# Baseplate.net
KiCad netlist of a schematic drawn in Altium Designer
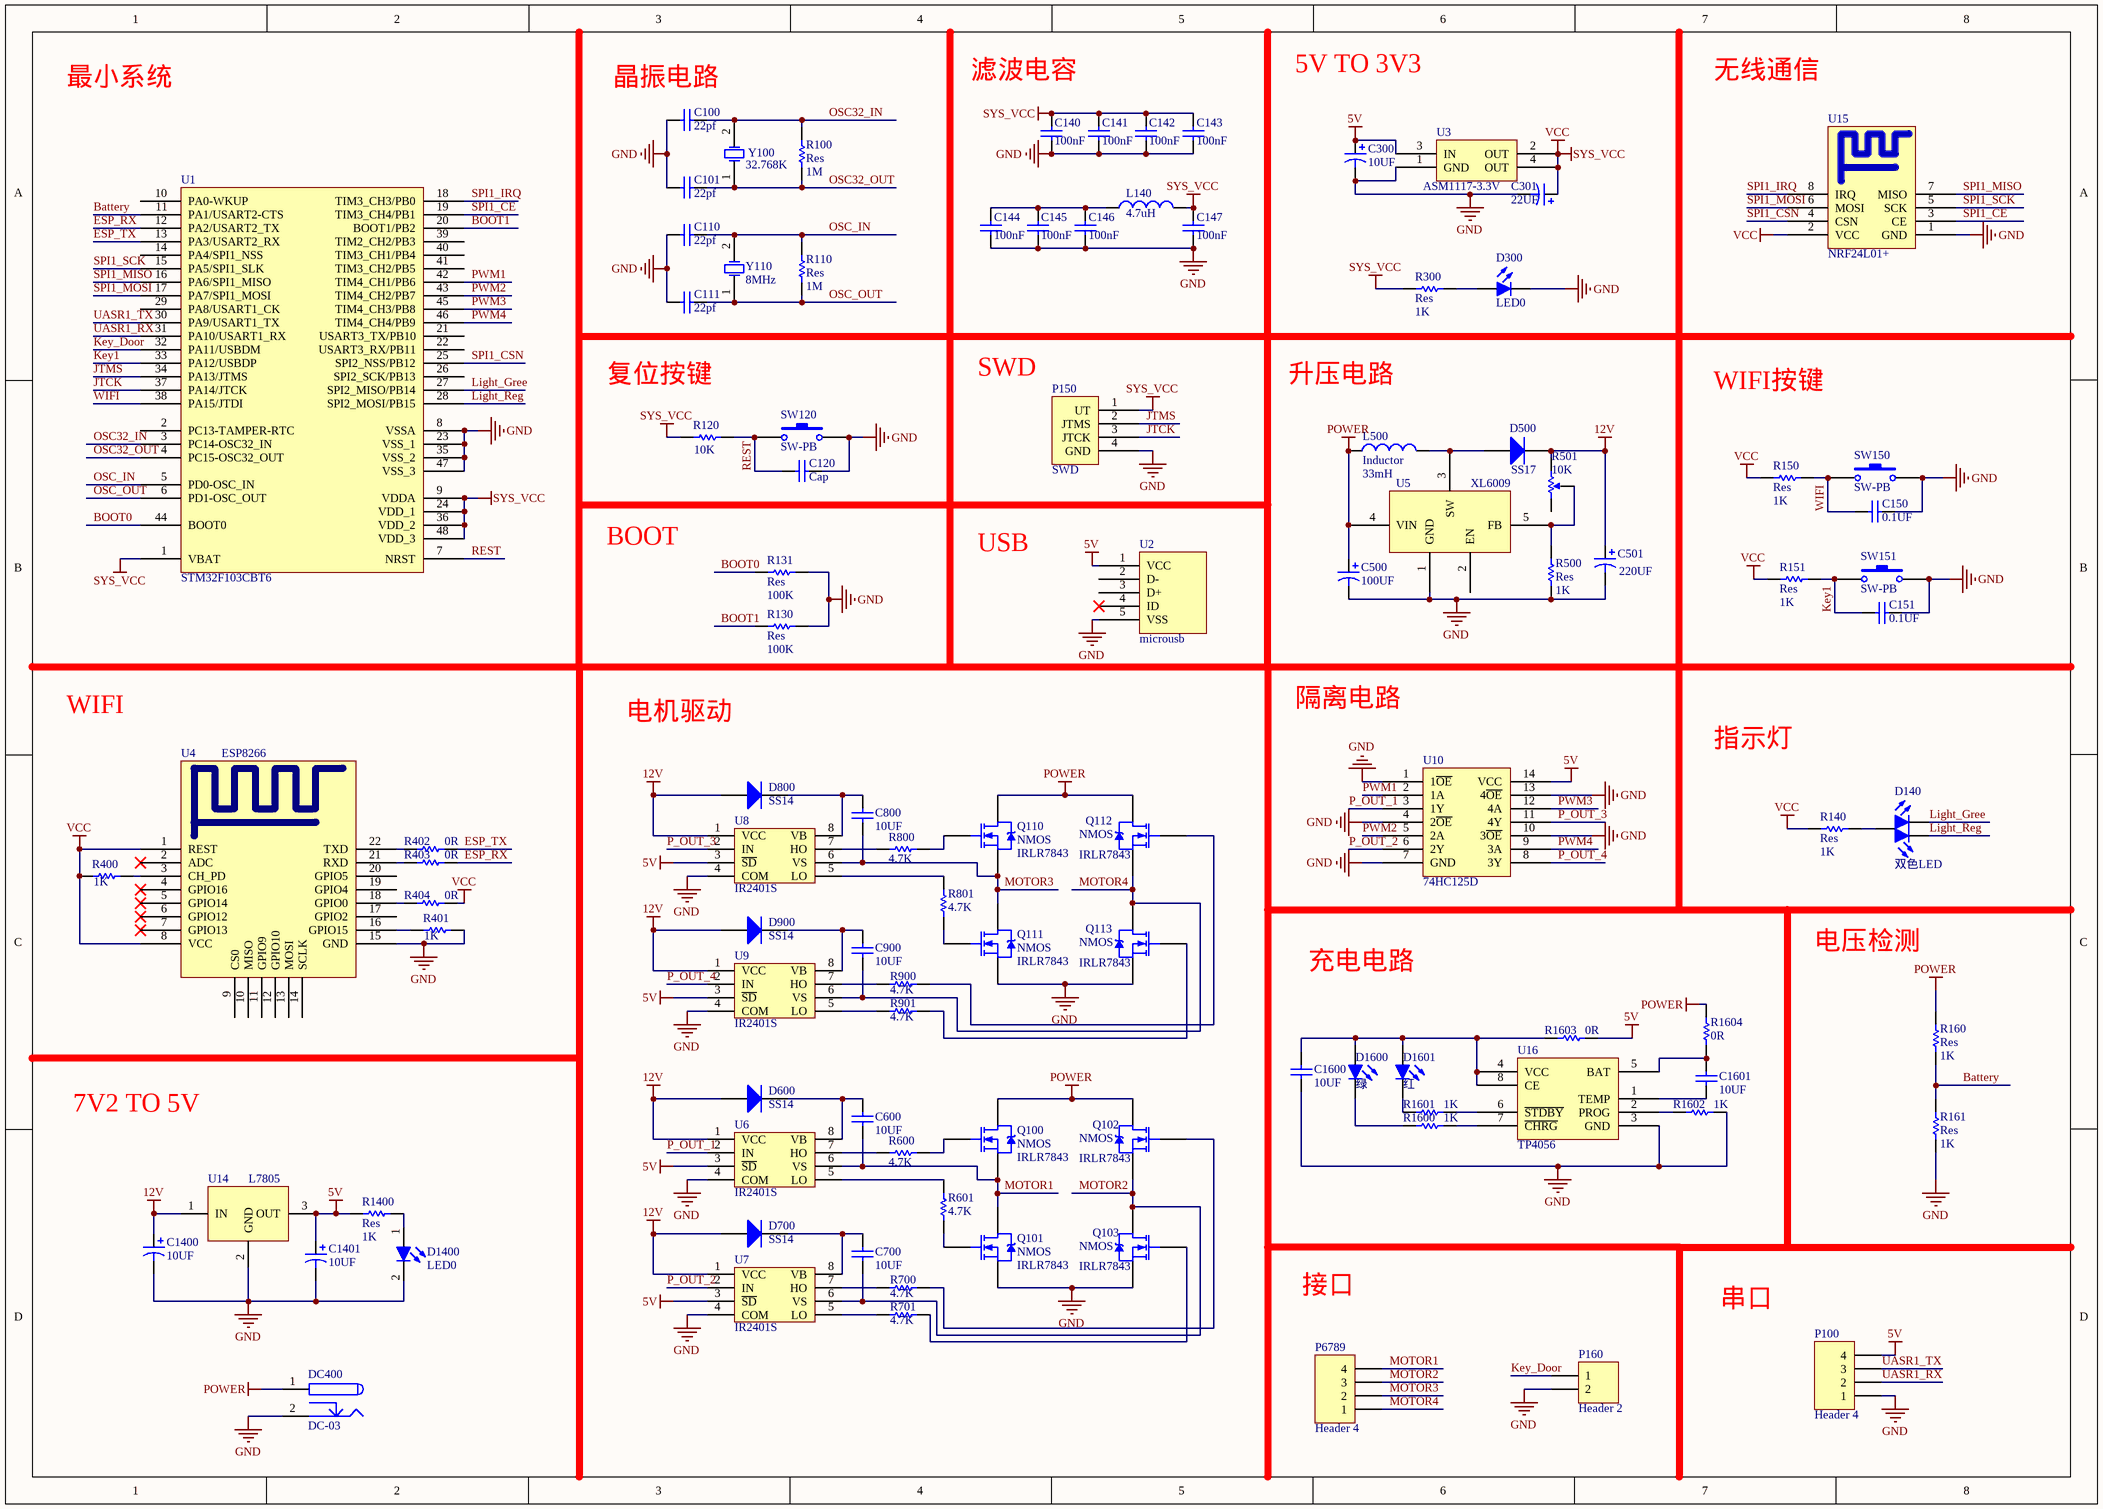
[diagram p0: Baseplate.SchDoc]

(export (version "E")
  (design (tool "Eeschema 10.0.6"))
  (components
    (comp (ref "C100")
      (value "22pf")
      (footprint "0805")
      (description "0805贴片电容")
      (libsource (lib "myintlib") (part "Cap"))
    )
    (comp (ref "C101")
      (value "22pf")
      (footprint "0805")
      (description "0805贴片电容")
      (libsource (lib "myintlib") (part "Cap"))
    )
    (comp (ref "C110")
      (value "22pf")
      (footprint "0805")
      (description "0805贴片电容")
      (libsource (lib "myintlib") (part "Cap"))
    )
    (comp (ref "C111")
      (value "22pf")
      (footprint "0805")
      (description "0805贴片电容")
      (libsource (lib "myintlib") (part "Cap"))
    )
    (comp (ref "C120")
      (value "Cap")
      (footprint "0805")
      (description "0805贴片电容")
      (libsource (lib "myintlib") (part "Cap"))
    )
    (comp (ref "C140")
      (value "100nF")
      (footprint "0805")
      (description "0805贴片电容")
      (libsource (lib "myintlib") (part "Cap"))
    )
    (comp (ref "C141")
      (value "100nF")
      (footprint "0805")
      (description "0805贴片电容")
      (libsource (lib "myintlib") (part "Cap"))
    )
    (comp (ref "C142")
      (value "100nF")
      (footprint "0805")
      (description "0805贴片电容")
      (libsource (lib "myintlib") (part "Cap"))
    )
    (comp (ref "C143")
      (value "100nF")
      (footprint "0805")
      (description "0805贴片电容")
      (libsource (lib "myintlib") (part "Cap"))
    )
    (comp (ref "C144")
      (value "100nF")
      (footprint "0805")
      (description "0805贴片电容")
      (libsource (lib "myintlib") (part "Cap"))
    )
    (comp (ref "C145")
      (value "100nF")
      (footprint "0805")
      (description "0805贴片电容")
      (libsource (lib "myintlib") (part "Cap"))
    )
    (comp (ref "C146")
      (value "100nF")
      (footprint "0805")
      (description "0805贴片电容")
      (libsource (lib "myintlib") (part "Cap"))
    )
    (comp (ref "C147")
      (value "100nF")
      (footprint "0805")
      (description "0805贴片电容")
      (libsource (lib "myintlib") (part "Cap"))
    )
    (comp (ref "C150")
      (value "0.1UF")
      (footprint "Cap0805")
      (description "0805贴片电容")
      (libsource (lib "myintlib") (part "Cap"))
    )
    (comp (ref "C151")
      (value "0.1UF")
      (footprint "Cap0805")
      (description "0805贴片电容")
      (libsource (lib "myintlib") (part "Cap"))
    )
    (comp (ref "C300")
      (value "10UF")
      (footprint "Cap0805")
      (description "10UF钽电容")
      (libsource (lib "myintlib") (part "Cap Pol3"))
    )
    (comp (ref "C301")
      (value "22UF")
      (footprint "Cap0805")
      (description "22UF钽电容")
      (libsource (lib "myintlib") (part "Cap Pol2"))
    )
    (comp (ref "C500")
      (value "100UF")
      (footprint "SMD6.3*7.7")
      (description "100UF电解电容")
      (libsource (lib "myintlib") (part "Cap Pol4"))
    )
    (comp (ref "C501")
      (value "Cap Pol5")
      (footprint "SMD8*10.5")
      (description "220UF电解电容")
      (fields (field (name "VAULE") "220UF"))
      (libsource (lib "myintlib") (part "Cap Pol5"))
    )
    (comp (ref "C600")
      (value "10UF")
      (footprint "0805")
      (description "0805贴片电容")
      (libsource (lib "myintlib") (part "Cap"))
    )
    (comp (ref "C700")
      (value "10UF")
      (footprint "0805")
      (description "0805贴片电容")
      (libsource (lib "myintlib") (part "Cap"))
    )
    (comp (ref "C800")
      (value "10UF")
      (footprint "0805")
      (description "0805贴片电容")
      (libsource (lib "myintlib") (part "Cap"))
    )
    (comp (ref "C900")
      (value "10UF")
      (footprint "0805")
      (description "0805贴片电容")
      (libsource (lib "myintlib") (part "Cap"))
    )
    (comp (ref "C1400")
      (value "10UF")
      (footprint "SMD4*4.5")
      (description "10UF钽电容")
      (libsource (lib "myintlib") (part "Cap Pol4"))
    )
    (comp (ref "C1401")
      (value "10UF")
      (footprint "SMD4*4.5")
      (description "10UF钽电容")
      (libsource (lib "myintlib") (part "Cap Pol4"))
    )
    (comp (ref "C1600")
      (value "10UF")
      (footprint "Cap0805")
      (description "0805贴片电容")
      (libsource (lib "myintlib") (part "Cap"))
    )
    (comp (ref "C1601")
      (value "10UF")
      (footprint "Cap0805")
      (description "0805贴片电容")
      (libsource (lib "myintlib") (part "Cap"))
    )
    (comp (ref "D140")
      (value "双色LED")
      (footprint "双色LED")
      (description "直插双色LED灯")
      (libsource (lib "myintlib") (part "双色LED"))
    )
    (comp (ref "D300")
      (value "LED0")
      (footprint "LED-0805")
      (description "0805贴片LED灯")
      (libsource (lib "myintlib") (part "LED0"))
    )
    (comp (ref "D500")
      (value "SS17")
      (footprint "DO-214AA")
      (description "1 Amp General Purpose Rectifier")
      (fields (field (name "PUBLISHER") "Altium Limited"))
      (libsource (lib "Miscellaneous Devices") (part "Diode 1N4007"))
    )
    (comp (ref "D600")
      (value "SS14")
      (footprint "DO-214AA")
      (description "肖特基二极管")
      (libsource (lib "myintlib") (part "Doide"))
    )
    (comp (ref "D700")
      (value "SS14")
      (footprint "DO-214AA")
      (description "肖特基二极管")
      (libsource (lib "myintlib") (part "Doide"))
    )
    (comp (ref "D800")
      (value "SS14")
      (footprint "DO-214AA")
      (description "肖特基二极管")
      (libsource (lib "myintlib") (part "Doide"))
    )
    (comp (ref "D900")
      (value "SS14")
      (footprint "DO-214AA")
      (description "肖特基二极管")
      (libsource (lib "myintlib") (part "Doide"))
    )
    (comp (ref "D1400")
      (value "LED0")
      (footprint "LED-0805")
      (description "0805贴片LED灯")
      (libsource (lib "") (part "LED0_1"))
    )
    (comp (ref "D1600")
      (value "绿")
      (footprint "LED-0805")
      (description "0805贴片LED灯")
      (libsource (lib "myintlib") (part "LED0"))
    )
    (comp (ref "D1601")
      (value "红")
      (footprint "LED-0805")
      (description "0805贴片LED灯")
      (libsource (lib "myintlib") (part "LED0"))
    )
    (comp (ref "DC400")
      (value "DC-03")
      (footprint "DC-003")
      (description "DC电源端子")
      (libsource (lib "myintlib") (part "DC-05"))
    )
    (comp (ref "L140")
      (value "4.7uH")
      (footprint "0805")
      (description "Inductor")
      (fields (field (name "PUBLISHER") "Altium Limited"))
      (libsource (lib "Miscellaneous Devices") (part "Inductor"))
    )
    (comp (ref "L500")
      (value "Inductor")
      (footprint "68uH-7*7")
      (fields (field (name "ALTIUM_VALUE") "33mH") (field (name "PUBLISHER") "Altium Limited"))
      (libsource (lib "Miscellaneous Devices") (part "Inductor"))
    )
    (comp (ref "P100")
      (value "Header 4")
      (footprint "HDR1X4")
      (description "Header, 4-Pin")
      (fields (field (name "PUBLISHER") "Altium Limited"))
      (libsource (lib "Miscellaneous Connectors") (part "Header 4"))
    )
    (comp (ref "P150")
      (value "SWD")
      (footprint "XH2.54-4P")
      (description "SWD下载端口")
      (libsource (lib "myintlib") (part "SWD"))
    )
    (comp (ref "P160")
      (value "Header 2")
      (footprint "HDR1X2")
      (description "Header, 2-Pin")
      (fields (field (name "PUBLISHER") "Altium Limited"))
      (libsource (lib "Miscellaneous Connectors") (part "Header 2"))
    )
    (comp (ref "P6789")
      (value "Header 4")
      (footprint "XH2.54-4P")
      (description "Header, 4-Pin")
      (fields (field (name "PUBLISHER") "Altium Limited"))
      (libsource (lib "Miscellaneous Connectors") (part "Header 4"))
    )
    (comp (ref "Q100")
      (value "NMOS")
      (footprint "DPAK/TO-252AA")
      (description "N沟MOS管")
      (fields (field (name "VAULE") "IRLR7843"))
      (libsource (lib "myintlib") (part "NMOS"))
    )
    (comp (ref "Q101")
      (value "NMOS")
      (footprint "DPAK/TO-252AA")
      (description "N沟MOS管")
      (fields (field (name "VAULE") "IRLR7843"))
      (libsource (lib "myintlib") (part "NMOS"))
    )
    (comp (ref "Q102")
      (value "NMOS")
      (footprint "DPAK/TO-252AA")
      (description "N沟MOS管")
      (fields (field (name "VAULE") "IRLR7843"))
      (libsource (lib "myintlib") (part "NMOS"))
    )
    (comp (ref "Q103")
      (value "NMOS")
      (footprint "DPAK/TO-252AA")
      (description "N沟MOS管")
      (fields (field (name "VAULE") "IRLR7843"))
      (libsource (lib "myintlib") (part "NMOS"))
    )
    (comp (ref "Q110")
      (value "NMOS")
      (footprint "DPAK/TO-252AA")
      (description "N沟MOS管")
      (fields (field (name "VAULE") "IRLR7843"))
      (libsource (lib "myintlib") (part "NMOS"))
    )
    (comp (ref "Q111")
      (value "NMOS")
      (footprint "DPAK/TO-252AA")
      (description "N沟MOS管")
      (fields (field (name "VAULE") "IRLR7843"))
      (libsource (lib "myintlib") (part "NMOS"))
    )
    (comp (ref "Q112")
      (value "NMOS")
      (footprint "DPAK/TO-252AA")
      (description "N沟MOS管")
      (fields (field (name "VAULE") "IRLR7843"))
      (libsource (lib "myintlib") (part "NMOS"))
    )
    (comp (ref "Q113")
      (value "NMOS")
      (footprint "DPAK/TO-252AA")
      (description "N沟MOS管")
      (fields (field (name "VAULE") "IRLR7843"))
      (libsource (lib "myintlib") (part "NMOS"))
    )
    (comp (ref "R100")
      (value "Res")
      (footprint "0805")
      (fields (field (name "ALTIUM_UNNAMED_1") "1M"))
      (libsource (lib "myintlib") (part "Res"))
    )
    (comp (ref "R110")
      (value "Res")
      (footprint "0805")
      (fields (field (name "ALTIUM_UNNAMED_1") "1M"))
      (libsource (lib "myintlib") (part "Res"))
    )
    (comp (ref "R120")
      (value "Res")
      (footprint "0805")
      (fields (field (name "ALTIUM_UNNAMED_1") "10K"))
      (libsource (lib "myintlib") (part "Res"))
    )
    (comp (ref "R130")
      (value "Res")
      (footprint "0805")
      (fields (field (name "ALTIUM_UNNAMED_1") "100K"))
      (libsource (lib "myintlib") (part "Res"))
    )
    (comp (ref "R131")
      (value "Res")
      (footprint "0805")
      (fields (field (name "ALTIUM_UNNAMED_1") "100K"))
      (libsource (lib "myintlib") (part "Res"))
    )
    (comp (ref "R140")
      (value "Res")
      (footprint "0805")
      (description "0805贴片电阻")
      (fields (field (name "VAULE") "1K"))
      (libsource (lib "myintlib") (part "Res"))
    )
    (comp (ref "R150")
      (value "Res")
      (footprint "0805")
      (description "0805贴片电阻")
      (fields (field (name "VAULE") "1K"))
      (libsource (lib "myintlib") (part "Res"))
    )
    (comp (ref "R151")
      (value "Res")
      (footprint "0805")
      (description "0805贴片电阻")
      (fields (field (name "VAULE") "1K"))
      (libsource (lib "myintlib") (part "Res"))
    )
    (comp (ref "R160")
      (value "Res")
      (footprint "0805")
      (description "0805贴片电阻")
      (fields (field (name "VAULE") "1K"))
      (libsource (lib "myintlib") (part "Res"))
    )
    (comp (ref "R161")
      (value "Res")
      (footprint "0805")
      (description "0805贴片电阻")
      (fields (field (name "VAULE") "1K"))
      (libsource (lib "myintlib") (part "Res"))
    )
    (comp (ref "R300")
      (value "Res")
      (footprint "0805")
      (fields (field (name "ALTIUM_UNNAMED_1") "1K"))
      (libsource (lib "myintlib") (part "Res"))
    )
    (comp (ref "R400")
      (value "Res")
      (footprint "0805")
      (description "0805贴片电阻")
      (fields (field (name "VAULE") "1K"))
      (libsource (lib "myintlib") (part "Res"))
    )
    (comp (ref "R401")
      (value "Res")
      (footprint "0805")
      (description "0805贴片电阻")
      (fields (field (name "VAULE") "1K"))
      (libsource (lib "myintlib") (part "Res"))
    )
    (comp (ref "R402")
      (value "Res")
      (footprint "0805")
      (description "0805贴片电阻")
      (fields (field (name "VAULE") "0R"))
      (libsource (lib "myintlib") (part "Res"))
    )
    (comp (ref "R403")
      (value "Res")
      (footprint "0805")
      (description "0805贴片电阻")
      (fields (field (name "VAULE") "0R"))
      (libsource (lib "myintlib") (part "Res"))
    )
    (comp (ref "R404")
      (value "Res")
      (footprint "0805")
      (description "0805贴片电阻")
      (fields (field (name "VAULE") "0R"))
      (libsource (lib "myintlib") (part "Res"))
    )
    (comp (ref "R500")
      (value "Res")
      (footprint "0805")
      (fields (field (name "ALTIUM_UNNAMED_1") "1K"))
      (libsource (lib "myintlib") (part "Res"))
    )
    (comp (ref "R501")
      (value "10K")
      (footprint "3296W")
      (description "3362电阻")
      (libsource (lib "myintlib") (part "ResAdj"))
    )
    (comp (ref "R600")
      (value "~")
      (footprint "0805")
      (fields (field (name "ALTIUM_UNNAMED_1") "4.7K"))
      (libsource (lib "myintlib") (part "Res"))
    )
    (comp (ref "R601")
      (value "~")
      (footprint "0805")
      (fields (field (name "ALTIUM_UNNAMED_1") "4.7K"))
      (libsource (lib "myintlib") (part "Res"))
    )
    (comp (ref "R700")
      (value "~")
      (footprint "0805")
      (fields (field (name "ALTIUM_UNNAMED_1") "4.7K"))
      (libsource (lib "myintlib") (part "Res"))
    )
    (comp (ref "R701")
      (value "~")
      (footprint "0805")
      (fields (field (name "ALTIUM_UNNAMED_1") "4.7K"))
      (libsource (lib "myintlib") (part "Res"))
    )
    (comp (ref "R800")
      (value "~")
      (footprint "0805")
      (fields (field (name "ALTIUM_UNNAMED_1") "4.7K"))
      (libsource (lib "myintlib") (part "Res"))
    )
    (comp (ref "R801")
      (value "~")
      (footprint "0805")
      (fields (field (name "ALTIUM_UNNAMED_1") "4.7K"))
      (libsource (lib "myintlib") (part "Res"))
    )
    (comp (ref "R900")
      (value "~")
      (footprint "0805")
      (fields (field (name "ALTIUM_UNNAMED_1") "4.7K"))
      (libsource (lib "myintlib") (part "Res"))
    )
    (comp (ref "R901")
      (value "~")
      (footprint "0805")
      (fields (field (name "ALTIUM_UNNAMED_1") "4.7K"))
      (libsource (lib "myintlib") (part "Res"))
    )
    (comp (ref "R1400")
      (value "Res")
      (footprint "0805")
      (fields (field (name "ALTIUM_UNNAMED_1") "1K"))
      (libsource (lib "myintlib") (part "Res"))
    )
    (comp (ref "R1600")
      (value "Res")
      (footprint "0805")
      (description "0805贴片电阻")
      (fields (field (name "VAULE") "1K"))
      (libsource (lib "myintlib") (part "Res"))
    )
    (comp (ref "R1601")
      (value "Res")
      (footprint "0805")
      (description "0805贴片电阻")
      (fields (field (name "VAULE") "1K"))
      (libsource (lib "myintlib") (part "Res"))
    )
    (comp (ref "R1602")
      (value "Res")
      (footprint "0805")
      (description "0805贴片电阻")
      (fields (field (name "VAULE") "1K"))
      (libsource (lib "myintlib") (part "Res"))
    )
    (comp (ref "R1603")
      (value "Res")
      (footprint "0805")
      (description "0805贴片电阻")
      (fields (field (name "VAULE") "0R"))
      (libsource (lib "myintlib") (part "Res"))
    )
    (comp (ref "R1604")
      (value "Res")
      (footprint "0805")
      (description "0805贴片电阻")
      (fields (field (name "VAULE") "0R"))
      (libsource (lib "myintlib") (part "Res"))
    )
    (comp (ref "SW120")
      (value "SW-PB")
      (footprint "SW-PB")
      (description "贴片按键")
      (libsource (lib "myintlib") (part "SW-PB"))
    )
    (comp (ref "SW150")
      (value "SW-PB")
      (footprint "SW-PB")
      (description "贴片按键")
      (libsource (lib "myintlib") (part "SW-PB"))
    )
    (comp (ref "SW151")
      (value "SW-PB")
      (footprint "SW-PB")
      (description "贴片按键")
      (libsource (lib "myintlib") (part "SW-PB"))
    )
    (comp (ref "U1")
      (value "STM32F103CBT6")
      (footprint "LQFP-48")
      (description "Cortex-M3内核单片机")
      (libsource (lib "myintlib") (part "STM32F103C8T6"))
    )
    (comp (ref "U2") (value "microusb") (footprint "microusb") (libsource (lib "myintlib") (part "microusb")))
    (comp (ref "U3")
      (value "ASM1117-3.3V")
      (footprint "SOT-223")
      (description "线性稳压芯片")
      (libsource (lib "myintlib") (part "ASM1117"))
    )
    (comp (ref "U4")
      (value "ESP8266")
      (footprint "myintlib:ESP8266")
      (description "串口wifi模块")
      (libsource (lib "myintlib") (part "ESP8266"))
    )
    (comp (ref "U5")
      (value "XL6009")
      (footprint "TO-263-5")
      (description "升压芯片")
      (libsource (lib "myintlib") (part "XL6009"))
    )
    (comp (ref "U6")
      (value "IR2401S")
      (footprint "myintlib:SOP8")
      (description "半桥驱动器")
      (libsource (lib "myintlib") (part "IR2401S"))
    )
    (comp (ref "U7")
      (value "IR2401S")
      (footprint "myintlib:SOP8")
      (description "半桥驱动器")
      (libsource (lib "myintlib") (part "IR2401S"))
    )
    (comp (ref "U8")
      (value "IR2401S")
      (footprint "myintlib:SOP8")
      (description "半桥驱动器")
      (libsource (lib "myintlib") (part "IR2401S"))
    )
    (comp (ref "U9")
      (value "IR2401S")
      (footprint "myintlib:SOP8")
      (description "半桥驱动器")
      (libsource (lib "myintlib") (part "IR2401S"))
    )
    (comp (ref "U10") (value "74HC125D") (footprint "SOP14") (libsource (lib "myintlib") (part "74HC125D")))
    (comp (ref "U14")
      (value "L7805")
      (footprint "TO-220-3")
      (description "5V线性稳压芯片")
      (libsource (lib "myintlib") (part "L7805"))
    )
    (comp (ref "U15")
      (value "NRF24L01+")
      (footprint "DIP8NRF")
      (description "直插式NRF")
      (libsource (lib "myintlib") (part "NRF24L01+"))
    )
    (comp (ref "U16")
      (value "TP4056")
      (footprint "SOP8")
      (description "锂电池充电芯片")
      (libsource (lib "myintlib") (part "TP4056"))
    )
    (comp (ref "Y100") (value "32.768K") (footprint "308晶振") (libsource (lib "myintlib") (part "32.768K")))
    (comp (ref "Y110")
      (value "8MHz")
      (footprint "X-HC49U")
      (description "无源晶振")
      (libsource (lib "myintlib") (part "XTAL"))
    )
  )
  (nets
    (net (code "1") (name "/BOOT0") (class "Default")
      (node (ref "R131") (pin "1") (pinfunction "1_1") (pintype "passive"))
      (node (ref "U1") (pin "44") (pinfunction "BOOT0_44") (pintype "passive"))
    )
    (net (code "2") (name "/BOOT1") (class "Default")
      (node (ref "R130") (pin "2") (pinfunction "2_2") (pintype "passive"))
      (node (ref "U1") (pin "20") (pinfunction "BOOT1/PB2_20") (pintype "passive"))
    )
    (net (code "3") (name "/Battery") (class "Default")
      (node (ref "R160") (pin "1") (pinfunction "1_1") (pintype "passive"))
      (node (ref "R161") (pin "2") (pinfunction "2_2") (pintype "passive"))
      (node (ref "U1") (pin "11") (pinfunction "PA1/USART2-CTS_11") (pintype "passive"))
    )
    (net (code "4") (name "/ESP_RX") (class "Default")
      (node (ref "R403") (pin "2") (pinfunction "2_2") (pintype "passive"))
      (node (ref "U1") (pin "12") (pinfunction "PA2/USART2_TX_12") (pintype "passive"))
    )
    (net (code "5") (name "/ESP_TX") (class "Default")
      (node (ref "R402") (pin "2") (pinfunction "2_2") (pintype "passive"))
      (node (ref "U1") (pin "13") (pinfunction "PA3/USART2_RX_13") (pintype "passive"))
    )
    (net (code "6") (name "/JTCK") (class "Default")
      (node (ref "P150") (pin "3") (pinfunction "JTCK_3") (pintype "power_in"))
      (node (ref "U1") (pin "37") (pinfunction "PA14/JTCK_37") (pintype "passive"))
    )
    (net (code "7") (name "/JTMS") (class "Default")
      (node (ref "P150") (pin "2") (pinfunction "JTMS_2") (pintype "power_in"))
      (node (ref "U1") (pin "34") (pinfunction "PA13/JTMS_34") (pintype "passive"))
    )
    (net (code "8") (name "/Key1") (class "Default")
      (node (ref "C151") (pin "1") (pinfunction "1_1") (pintype "passive"))
      (node (ref "R151") (pin "2") (pinfunction "2_2") (pintype "passive"))
      (node (ref "SW151") (pin "1") (pinfunction "1_1") (pintype "passive"))
      (node (ref "U1") (pin "33") (pinfunction "PA12/USBDP_33") (pintype "passive"))
    )
    (net (code "9") (name "/Key_Door") (class "Default")
      (node (ref "P160") (pin "1") (pinfunction "1_1") (pintype "passive"))
      (node (ref "U1") (pin "32") (pinfunction "PA11/USBDM_32") (pintype "passive"))
    )
    (net (code "10") (name "/Light_Gree") (class "Default")
      (node (ref "D140") (pin "1") (pinfunction "A_1") (pintype "passive"))
      (node (ref "U1") (pin "27") (pinfunction "SPI2_MISO/PB14_27") (pintype "passive"))
    )
    (net (code "11") (name "/Light_Reg") (class "Default")
      (node (ref "D140") (pin "3") (pinfunction "A_3") (pintype "passive"))
      (node (ref "U1") (pin "28") (pinfunction "SPI2_MOSI/PB15_28") (pintype "passive"))
    )
    (net (code "12") (name "/MOTOR1") (class "Default")
      (node (ref "C600") (pin "2") (pinfunction "2_2") (pintype "passive"))
      (node (ref "P6789") (pin "4") (pinfunction "4_4") (pintype "passive"))
      (node (ref "Q100") (pin "3") (pinfunction "S_3") (pintype "passive"))
      (node (ref "Q101") (pin "2") (pinfunction "D_2") (pintype "passive"))
      (node (ref "U6") (pin "6") (pinfunction "VS_6") (pintype "passive"))
    )
    (net (code "13") (name "/MOTOR2") (class "Default")
      (node (ref "C700") (pin "2") (pinfunction "2_2") (pintype "passive"))
      (node (ref "P6789") (pin "3") (pinfunction "3_3") (pintype "passive"))
      (node (ref "Q102") (pin "3") (pinfunction "S_3") (pintype "passive"))
      (node (ref "Q103") (pin "2") (pinfunction "D_2") (pintype "passive"))
      (node (ref "U7") (pin "6") (pinfunction "VS_6") (pintype "passive"))
    )
    (net (code "14") (name "/MOTOR3") (class "Default")
      (node (ref "C800") (pin "2") (pinfunction "2_2") (pintype "passive"))
      (node (ref "P6789") (pin "2") (pinfunction "2_2") (pintype "passive"))
      (node (ref "Q110") (pin "3") (pinfunction "S_3") (pintype "passive"))
      (node (ref "Q111") (pin "2") (pinfunction "D_2") (pintype "passive"))
      (node (ref "U8") (pin "6") (pinfunction "VS_6") (pintype "passive"))
    )
    (net (code "15") (name "/MOTOR4") (class "Default")
      (node (ref "C900") (pin "2") (pinfunction "2_2") (pintype "passive"))
      (node (ref "P6789") (pin "1") (pinfunction "1_1") (pintype "passive"))
      (node (ref "Q112") (pin "3") (pinfunction "S_3") (pintype "passive"))
      (node (ref "Q113") (pin "2") (pinfunction "D_2") (pintype "passive"))
      (node (ref "U9") (pin "6") (pinfunction "VS_6") (pintype "passive"))
    )
    (net (code "16") (name "/OSC32_IN") (class "Default")
      (node (ref "C100") (pin "2") (pinfunction "2_2") (pintype "passive"))
      (node (ref "R100") (pin "2") (pinfunction "2_2") (pintype "passive"))
      (node (ref "U1") (pin "3") (pinfunction "PC14-OSC32_IN_3") (pintype "passive"))
      (node (ref "Y100") (pin "2") (pinfunction "OSC2_2") (pintype "passive"))
    )
    (net (code "17") (name "/OSC32_OUT") (class "Default")
      (node (ref "C101") (pin "2") (pinfunction "2_2") (pintype "passive"))
      (node (ref "R100") (pin "1") (pinfunction "1_1") (pintype "passive"))
      (node (ref "U1") (pin "4") (pinfunction "PC15-OSC32_OUT_4") (pintype "passive"))
      (node (ref "Y100") (pin "1") (pinfunction "OSC1_1") (pintype "passive"))
    )
    (net (code "18") (name "/OSC_IN") (class "Default")
      (node (ref "C110") (pin "2") (pinfunction "2_2") (pintype "passive"))
      (node (ref "R110") (pin "2") (pinfunction "2_2") (pintype "passive"))
      (node (ref "U1") (pin "5") (pinfunction "PD0-OSC_IN_5") (pintype "passive"))
      (node (ref "Y110") (pin "2") (pinfunction "OSC2_2") (pintype "passive"))
    )
    (net (code "19") (name "/OSC_OUT") (class "Default")
      (node (ref "C111") (pin "2") (pinfunction "2_2") (pintype "passive"))
      (node (ref "R110") (pin "1") (pinfunction "1_1") (pintype "passive"))
      (node (ref "U1") (pin "6") (pinfunction "PD1-OSC_OUT_6") (pintype "passive"))
      (node (ref "Y110") (pin "1") (pinfunction "OSC1_1") (pintype "passive"))
    )
    (net (code "20") (name "/PWM1") (class "Default")
      (node (ref "U1") (pin "42") (pinfunction "TIM4_CH1/PB6_42") (pintype "passive"))
      (node (ref "U10") (pin "2") (pinfunction "1A_2") (pintype "passive"))
    )
    (net (code "21") (name "/PWM2") (class "Default")
      (node (ref "U1") (pin "43") (pinfunction "TIM4_CH2/PB7_43") (pintype "passive"))
      (node (ref "U10") (pin "5") (pinfunction "2A_5") (pintype "passive"))
    )
    (net (code "22") (name "/PWM3") (class "Default")
      (node (ref "U1") (pin "45") (pinfunction "TIM4_CH3/PB8_45") (pintype "passive"))
      (node (ref "U10") (pin "12") (pinfunction "4A_12") (pintype "passive"))
    )
    (net (code "23") (name "/PWM4") (class "Default")
      (node (ref "U1") (pin "46") (pinfunction "TIM4_CH4/PB9_46") (pintype "passive"))
      (node (ref "U10") (pin "9") (pinfunction "3A_9") (pintype "passive"))
    )
    (net (code "24") (name "/P_OUT_1") (class "Default")
      (node (ref "U10") (pin "3") (pinfunction "1Y_3") (pintype "passive"))
      (node (ref "U6") (pin "2") (pinfunction "IN_2") (pintype "passive"))
    )
    (net (code "25") (name "/P_OUT_2") (class "Default")
      (node (ref "U10") (pin "6") (pinfunction "2Y_6") (pintype "passive"))
      (node (ref "U7") (pin "2") (pinfunction "IN_2") (pintype "passive"))
    )
    (net (code "26") (name "/P_OUT_3") (class "Default")
      (node (ref "U10") (pin "11") (pinfunction "4Y_11") (pintype "passive"))
      (node (ref "U8") (pin "2") (pinfunction "IN_2") (pintype "passive"))
    )
    (net (code "27") (name "/P_OUT_4") (class "Default")
      (node (ref "U10") (pin "8") (pinfunction "3Y_8") (pintype "passive"))
      (node (ref "U9") (pin "2") (pinfunction "IN_2") (pintype "passive"))
    )
    (net (code "28") (name "/REST") (class "Default")
      (node (ref "C120") (pin "1") (pinfunction "1_1") (pintype "passive"))
      (node (ref "R120") (pin "2") (pinfunction "2_2") (pintype "passive"))
      (node (ref "SW120") (pin "1") (pinfunction "1_1") (pintype "passive"))
      (node (ref "U1") (pin "7") (pinfunction "NRST_7") (pintype "passive"))
    )
    (net (code "29") (name "/SPI1_CE") (class "Default")
      (node (ref "U1") (pin "19") (pinfunction "TIM3_CH4/PB1_19") (pintype "passive"))
      (node (ref "U15") (pin "3") (pinfunction "CE_3") (pintype "passive"))
    )
    (net (code "30") (name "/SPI1_CSN") (class "Default")
      (node (ref "U1") (pin "25") (pinfunction "SPI2_NSS/PB12_25") (pintype "passive"))
      (node (ref "U15") (pin "4") (pinfunction "CSN_4") (pintype "passive"))
    )
    (net (code "31") (name "/SPI1_IRQ") (class "Default")
      (node (ref "U1") (pin "18") (pinfunction "TIM3_CH3/PB0_18") (pintype "passive"))
      (node (ref "U15") (pin "8") (pinfunction "IRQ_8") (pintype "passive"))
    )
    (net (code "32") (name "/SPI1_MISO") (class "Default")
      (node (ref "U1") (pin "16") (pinfunction "PA6/SPI1_MISO_16") (pintype "passive"))
      (node (ref "U15") (pin "7") (pinfunction "MISO_7") (pintype "passive"))
    )
    (net (code "33") (name "/SPI1_MOSI") (class "Default")
      (node (ref "U1") (pin "17") (pinfunction "PA7/SPI1_MOSI_17") (pintype "passive"))
      (node (ref "U15") (pin "6") (pinfunction "MOSI_6") (pintype "passive"))
    )
    (net (code "34") (name "/SPI1_SCK") (class "Default")
      (node (ref "U1") (pin "15") (pinfunction "PA5/SPI1_SLK_15") (pintype "passive"))
      (node (ref "U15") (pin "5") (pinfunction "SCK_5") (pintype "passive"))
    )
    (net (code "35") (name "/UASR1_RX") (class "Default")
      (node (ref "P100") (pin "2") (pinfunction "2_2") (pintype "passive"))
      (node (ref "U1") (pin "31") (pinfunction "PA10/USART1_RX_31") (pintype "passive"))
    )
    (net (code "36") (name "/UASR1_TX") (class "Default")
      (node (ref "P100") (pin "3") (pinfunction "3_3") (pintype "passive"))
      (node (ref "U1") (pin "30") (pinfunction "PA9/USART1_TX_30") (pintype "passive"))
    )
    (net (code "37") (name "/WIFI") (class "Default")
      (node (ref "C150") (pin "1") (pinfunction "1_1") (pintype "passive"))
      (node (ref "R150") (pin "2") (pinfunction "2_2") (pintype "passive"))
      (node (ref "SW150") (pin "1") (pinfunction "1_1") (pintype "passive"))
      (node (ref "U1") (pin "38") (pinfunction "PA15/JTDI_38") (pintype "passive"))
    )
    (net (code "38") (name "5V") (class "Default")
      (node (ref "C1401") (pin "1") (pinfunction "1_1") (pintype "passive"))
      (node (ref "C300") (pin "1") (pinfunction "1_1") (pintype "passive"))
      (node (ref "P100") (pin "4") (pinfunction "4_4") (pintype "passive"))
      (node (ref "R1400") (pin "2") (pinfunction "2_2") (pintype "passive"))
      (node (ref "R1603") (pin "2") (pinfunction "2_2") (pintype "passive"))
      (node (ref "U10") (pin "14") (pinfunction "VCC_14") (pintype "passive"))
      (node (ref "U14") (pin "3") (pinfunction "OUT_3") (pintype "passive"))
      (node (ref "U2") (pin "1") (pinfunction "VCC_1") (pintype "passive"))
      (node (ref "U3") (pin "3") (pinfunction "IN_3") (pintype "passive"))
      (node (ref "U6") (pin "3") (pinfunction "~{SD}_3") (pintype "passive"))
      (node (ref "U7") (pin "3") (pinfunction "~{SD}_3") (pintype "passive"))
      (node (ref "U8") (pin "3") (pinfunction "~{SD}_3") (pintype "passive"))
      (node (ref "U9") (pin "3") (pinfunction "~{SD}_3") (pintype "passive"))
    )
    (net (code "39") (name "12V") (class "Default")
      (node (ref "C1400") (pin "1") (pinfunction "1_1") (pintype "passive"))
      (node (ref "C501") (pin "1") (pinfunction "1_1") (pintype "passive"))
      (node (ref "D500") (pin "2") (pinfunction "K_2") (pintype "passive"))
      (node (ref "D600") (pin "1") (pinfunction "A_1") (pintype "passive"))
      (node (ref "D700") (pin "1") (pinfunction "A_1") (pintype "passive"))
      (node (ref "D800") (pin "1") (pinfunction "A_1") (pintype "passive"))
      (node (ref "D900") (pin "1") (pinfunction "A_1") (pintype "passive"))
      (node (ref "R501") (pin "1") (pinfunction "1_1") (pintype "passive"))
      (node (ref "U14") (pin "1") (pinfunction "IN_1") (pintype "passive"))
      (node (ref "U6") (pin "1") (pinfunction "VCC_1") (pintype "passive"))
      (node (ref "U7") (pin "1") (pinfunction "VCC_1") (pintype "passive"))
      (node (ref "U8") (pin "1") (pinfunction "VCC_1") (pintype "passive"))
      (node (ref "U9") (pin "1") (pinfunction "VCC_1") (pintype "passive"))
    )
    (net (code "40") (name "GND") (class "Default")
      (node (ref "C100") (pin "1") (pinfunction "1_1") (pintype "passive"))
      (node (ref "C101") (pin "1") (pinfunction "1_1") (pintype "passive"))
      (node (ref "C110") (pin "1") (pinfunction "1_1") (pintype "passive"))
      (node (ref "C111") (pin "1") (pinfunction "1_1") (pintype "passive"))
      (node (ref "C120") (pin "2") (pinfunction "2_2") (pintype "passive"))
      (node (ref "C140") (pin "1") (pinfunction "1_1") (pintype "passive"))
      (node (ref "C1400") (pin "2") (pinfunction "2_2") (pintype "passive"))
      (node (ref "C1401") (pin "2") (pinfunction "2_2") (pintype "passive"))
      (node (ref "C141") (pin "1") (pinfunction "1_1") (pintype "passive"))
      (node (ref "C142") (pin "1") (pinfunction "1_1") (pintype "passive"))
      (node (ref "C143") (pin "1") (pinfunction "1_1") (pintype "passive"))
      (node (ref "C144") (pin "1") (pinfunction "1_1") (pintype "passive"))
      (node (ref "C145") (pin "1") (pinfunction "1_1") (pintype "passive"))
      (node (ref "C146") (pin "1") (pinfunction "1_1") (pintype "passive"))
      (node (ref "C147") (pin "1") (pinfunction "1_1") (pintype "passive"))
      (node (ref "C150") (pin "2") (pinfunction "2_2") (pintype "passive"))
      (node (ref "C151") (pin "2") (pinfunction "2_2") (pintype "passive"))
      (node (ref "C1600") (pin "1") (pinfunction "1_1") (pintype "passive"))
      (node (ref "C300") (pin "2") (pinfunction "2_2") (pintype "passive"))
      (node (ref "C301") (pin "2") (pinfunction "2_2") (pintype "passive"))
      (node (ref "C500") (pin "2") (pinfunction "2_2") (pintype "passive"))
      (node (ref "C501") (pin "2") (pinfunction "2_2") (pintype "passive"))
      (node (ref "D1400") (pin "2") (pinfunction "K_2") (pintype "passive"))
      (node (ref "D300") (pin "2") (pinfunction "K_2") (pintype "passive"))
      (node (ref "DC400") (pin "2") (pinfunction "2_2") (pintype "power_in"))
      (node (ref "P100") (pin "1") (pinfunction "1_1") (pintype "passive"))
      (node (ref "P150") (pin "4") (pinfunction "GND_4") (pintype "power_in"))
      (node (ref "P160") (pin "2") (pinfunction "2_2") (pintype "passive"))
      (node (ref "Q101") (pin "3") (pinfunction "S_3") (pintype "passive"))
      (node (ref "Q103") (pin "3") (pinfunction "S_3") (pintype "passive"))
      (node (ref "Q111") (pin "3") (pinfunction "S_3") (pintype "passive"))
      (node (ref "Q113") (pin "3") (pinfunction "S_3") (pintype "passive"))
      (node (ref "R130") (pin "1") (pinfunction "1_1") (pintype "passive"))
      (node (ref "R131") (pin "2") (pinfunction "2_2") (pintype "passive"))
      (node (ref "R1602") (pin "2") (pinfunction "2_2") (pintype "passive"))
      (node (ref "R161") (pin "1") (pinfunction "1_1") (pintype "passive"))
      (node (ref "R401") (pin "2") (pinfunction "2_2") (pintype "passive"))
      (node (ref "R500") (pin "1") (pinfunction "1_1") (pintype "passive"))
      (node (ref "SW120") (pin "2") (pinfunction "2_2") (pintype "passive"))
      (node (ref "SW150") (pin "2") (pinfunction "2_2") (pintype "passive"))
      (node (ref "SW151") (pin "2") (pinfunction "2_2") (pintype "passive"))
      (node (ref "U1") (pin "23") (pinfunction "VSS_1_23") (pintype "passive"))
      (node (ref "U1") (pin "35") (pinfunction "VSS_2_35") (pintype "passive"))
      (node (ref "U1") (pin "47") (pinfunction "VSS_3_47") (pintype "passive"))
      (node (ref "U1") (pin "8") (pinfunction "VSSA_8") (pintype "passive"))
      (node (ref "U10") (pin "1") (pinfunction "1~{OE}_1") (pintype "passive"))
      (node (ref "U10") (pin "10") (pinfunction "3~{OE}_10") (pintype "passive"))
      (node (ref "U10") (pin "13") (pinfunction "4~{OE}_13") (pintype "passive"))
      (node (ref "U10") (pin "4") (pinfunction "2~{OE}_4") (pintype "passive"))
      (node (ref "U10") (pin "7") (pinfunction "GND_7") (pintype "passive"))
      (node (ref "U14") (pin "2") (pinfunction "GND_2") (pintype "passive"))
      (node (ref "U15") (pin "1") (pinfunction "GND_1") (pintype "passive"))
      (node (ref "U16") (pin "3") (pinfunction "GND_3") (pintype "passive"))
      (node (ref "U2") (pin "5") (pinfunction "VSS_5") (pintype "passive"))
      (node (ref "U3") (pin "1") (pinfunction "GND_1") (pintype "passive"))
      (node (ref "U4") (pin "15") (pinfunction "GND_15") (pintype "passive"))
      (node (ref "U5") (pin "1") (pinfunction "GND_1") (pintype "passive"))
      (node (ref "U6") (pin "4") (pinfunction "COM_4") (pintype "passive"))
      (node (ref "U7") (pin "4") (pinfunction "COM_4") (pintype "passive"))
      (node (ref "U8") (pin "4") (pinfunction "COM_4") (pintype "passive"))
      (node (ref "U9") (pin "4") (pinfunction "COM_4") (pintype "passive"))
    )
    (net (code "41") (name "Net-(C144-Pad2)") (class "Default")
      (node (ref "C144") (pin "2") (pinfunction "2_2") (pintype "passive"))
      (node (ref "C145") (pin "2") (pinfunction "2_2") (pintype "passive"))
      (node (ref "C146") (pin "2") (pinfunction "2_2") (pintype "passive"))
      (node (ref "L140") (pin "1") (pinfunction "1_1") (pintype "passive"))
    )
    (net (code "42") (name "Net-(D140-K)") (class "Default")
      (node (ref "D140") (pin "2") (pinfunction "K_2") (pintype "passive"))
      (node (ref "R140") (pin "2") (pinfunction "2_2") (pintype "passive"))
    )
    (net (code "43") (name "Net-(D300-A)") (class "Default")
      (node (ref "D300") (pin "1") (pinfunction "A_1") (pintype "passive"))
      (node (ref "R300") (pin "2") (pinfunction "2_2") (pintype "passive"))
    )
    (net (code "44") (name "Net-(D500-A)") (class "Default")
      (node (ref "D500") (pin "1") (pinfunction "A_1") (pintype "passive"))
      (node (ref "L500") (pin "2") (pinfunction "2_2") (pintype "passive"))
      (node (ref "U5") (pin "3") (pinfunction "SW_3") (pintype "passive"))
    )
    (net (code "45") (name "Net-(D600-K)") (class "Default")
      (node (ref "C600") (pin "1") (pinfunction "1_1") (pintype "passive"))
      (node (ref "D600") (pin "2") (pinfunction "K_2") (pintype "passive"))
      (node (ref "U6") (pin "8") (pinfunction "VB_8") (pintype "passive"))
    )
    (net (code "46") (name "Net-(D700-K)") (class "Default")
      (node (ref "C700") (pin "1") (pinfunction "1_1") (pintype "passive"))
      (node (ref "D700") (pin "2") (pinfunction "K_2") (pintype "passive"))
      (node (ref "U7") (pin "8") (pinfunction "VB_8") (pintype "passive"))
    )
    (net (code "47") (name "Net-(D800-K)") (class "Default")
      (node (ref "C800") (pin "1") (pinfunction "1_1") (pintype "passive"))
      (node (ref "D800") (pin "2") (pinfunction "K_2") (pintype "passive"))
      (node (ref "U8") (pin "8") (pinfunction "VB_8") (pintype "passive"))
    )
    (net (code "48") (name "Net-(D900-K)") (class "Default")
      (node (ref "C900") (pin "1") (pinfunction "1_1") (pintype "passive"))
      (node (ref "D900") (pin "2") (pinfunction "K_2") (pintype "passive"))
      (node (ref "U9") (pin "8") (pinfunction "VB_8") (pintype "passive"))
    )
    (net (code "49") (name "Net-(D1400-A)") (class "Default")
      (node (ref "D1400") (pin "1") (pinfunction "A_1") (pintype "passive"))
      (node (ref "R1400") (pin "1") (pinfunction "1_1") (pintype "passive"))
    )
    (net (code "50") (name "Net-(D1600-A)") (class "Default")
      (node (ref "C1600") (pin "2") (pinfunction "2_2") (pintype "passive"))
      (node (ref "D1600") (pin "1") (pinfunction "A_1") (pintype "passive"))
      (node (ref "D1601") (pin "1") (pinfunction "A_1") (pintype "passive"))
      (node (ref "R1603") (pin "1") (pinfunction "1_1") (pintype "passive"))
      (node (ref "U16") (pin "4") (pinfunction "VCC_4") (pintype "passive"))
      (node (ref "U16") (pin "8") (pinfunction "CE_8") (pintype "passive"))
    )
    (net (code "51") (name "Net-(D1600-K)") (class "Default")
      (node (ref "D1600") (pin "2") (pinfunction "K_2") (pintype "passive"))
      (node (ref "R1600") (pin "1") (pinfunction "1_1") (pintype "passive"))
    )
    (net (code "52") (name "Net-(D1601-K)") (class "Default")
      (node (ref "D1601") (pin "2") (pinfunction "K_2") (pintype "passive"))
      (node (ref "R1601") (pin "1") (pinfunction "1_1") (pintype "passive"))
    )
    (net (code "53") (name "Net-(Q100-G)") (class "Default")
      (node (ref "Q100") (pin "1") (pinfunction "G_1") (pintype "passive"))
      (node (ref "R600") (pin "1") (pinfunction "1_1") (pintype "passive"))
    )
    (net (code "54") (name "Net-(Q101-G)") (class "Default")
      (node (ref "Q101") (pin "1") (pinfunction "G_1") (pintype "passive"))
      (node (ref "R601") (pin "1") (pinfunction "1_1") (pintype "passive"))
    )
    (net (code "55") (name "Net-(Q102-G)") (class "Default")
      (node (ref "Q102") (pin "1") (pinfunction "G_1") (pintype "passive"))
      (node (ref "R700") (pin "1") (pinfunction "1_1") (pintype "passive"))
    )
    (net (code "56") (name "Net-(Q103-G)") (class "Default")
      (node (ref "Q103") (pin "1") (pinfunction "G_1") (pintype "passive"))
      (node (ref "R701") (pin "1") (pinfunction "1_1") (pintype "passive"))
    )
    (net (code "57") (name "Net-(Q110-G)") (class "Default")
      (node (ref "Q110") (pin "1") (pinfunction "G_1") (pintype "passive"))
      (node (ref "R800") (pin "1") (pinfunction "1_1") (pintype "passive"))
    )
    (net (code "58") (name "Net-(Q111-G)") (class "Default")
      (node (ref "Q111") (pin "1") (pinfunction "G_1") (pintype "passive"))
      (node (ref "R801") (pin "1") (pinfunction "1_1") (pintype "passive"))
    )
    (net (code "59") (name "Net-(Q112-G)") (class "Default")
      (node (ref "Q112") (pin "1") (pinfunction "G_1") (pintype "passive"))
      (node (ref "R900") (pin "1") (pinfunction "1_1") (pintype "passive"))
    )
    (net (code "60") (name "Net-(Q113-G)") (class "Default")
      (node (ref "Q113") (pin "1") (pinfunction "G_1") (pintype "passive"))
      (node (ref "R901") (pin "1") (pinfunction "1_1") (pintype "passive"))
    )
    (net (code "61") (name "Net-(U4-CH_PD)") (class "Default")
      (node (ref "R400") (pin "2") (pinfunction "2_2") (pintype "passive"))
      (node (ref "U4") (pin "3") (pinfunction "CH_PD_3") (pintype "passive"))
    )
    (net (code "62") (name "Net-(U4-GPIO0)") (class "Default")
      (node (ref "R404") (pin "1") (pinfunction "1_1") (pintype "passive"))
      (node (ref "U4") (pin "18") (pinfunction "GPIO0_18") (pintype "passive"))
    )
    (net (code "63") (name "Net-(U4-GPIO15)") (class "Default")
      (node (ref "R401") (pin "1") (pinfunction "1_1") (pintype "passive"))
      (node (ref "U4") (pin "16") (pinfunction "GPIO15_16") (pintype "passive"))
    )
    (net (code "64") (name "Net-(U4-RXD)") (class "Default")
      (node (ref "R403") (pin "1") (pinfunction "1_1") (pintype "passive"))
      (node (ref "U4") (pin "21") (pinfunction "RXD_21") (pintype "passive"))
    )
    (net (code "65") (name "Net-(U4-TXD)") (class "Default")
      (node (ref "R402") (pin "1") (pinfunction "1_1") (pintype "passive"))
      (node (ref "U4") (pin "22") (pinfunction "TXD_22") (pintype "passive"))
    )
    (net (code "66") (name "Net-(U5-FB)") (class "Default")
      (node (ref "R500") (pin "2") (pinfunction "2_2") (pintype "passive"))
      (node (ref "R501") (pin "2") (pinfunction "2_2") (pintype "passive"))
      (node (ref "U5") (pin "5") (pinfunction "FB_5") (pintype "passive"))
    )
    (net (code "67") (name "Net-(U6-HO)") (class "Default")
      (node (ref "R600") (pin "2") (pinfunction "2_2") (pintype "passive"))
      (node (ref "U6") (pin "7") (pinfunction "HO_7") (pintype "passive"))
    )
    (net (code "68") (name "Net-(U6-LO)") (class "Default")
      (node (ref "R601") (pin "2") (pinfunction "2_2") (pintype "passive"))
      (node (ref "U6") (pin "5") (pinfunction "LO_5") (pintype "passive"))
    )
    (net (code "69") (name "Net-(U7-HO)") (class "Default")
      (node (ref "R700") (pin "2") (pinfunction "2_2") (pintype "passive"))
      (node (ref "U7") (pin "7") (pinfunction "HO_7") (pintype "passive"))
    )
    (net (code "70") (name "Net-(U7-LO)") (class "Default")
      (node (ref "R701") (pin "2") (pinfunction "2_2") (pintype "passive"))
      (node (ref "U7") (pin "5") (pinfunction "LO_5") (pintype "passive"))
    )
    (net (code "71") (name "Net-(U8-HO)") (class "Default")
      (node (ref "R800") (pin "2") (pinfunction "2_2") (pintype "passive"))
      (node (ref "U8") (pin "7") (pinfunction "HO_7") (pintype "passive"))
    )
    (net (code "72") (name "Net-(U8-LO)") (class "Default")
      (node (ref "R801") (pin "2") (pinfunction "2_2") (pintype "passive"))
      (node (ref "U8") (pin "5") (pinfunction "LO_5") (pintype "passive"))
    )
    (net (code "73") (name "Net-(U9-HO)") (class "Default")
      (node (ref "R900") (pin "2") (pinfunction "2_2") (pintype "passive"))
      (node (ref "U9") (pin "7") (pinfunction "HO_7") (pintype "passive"))
    )
    (net (code "74") (name "Net-(U9-LO)") (class "Default")
      (node (ref "R901") (pin "2") (pinfunction "2_2") (pintype "passive"))
      (node (ref "U9") (pin "5") (pinfunction "LO_5") (pintype "passive"))
    )
    (net (code "75") (name "Net-(U16-BAT)") (class "Default")
      (node (ref "C1601") (pin "2") (pinfunction "2_2") (pintype "passive"))
      (node (ref "R1604") (pin "1") (pinfunction "1_1") (pintype "passive"))
      (node (ref "U16") (pin "5") (pinfunction "BAT_5") (pintype "passive"))
    )
    (net (code "76") (name "Net-(U16-PROG)") (class "Default")
      (node (ref "R1602") (pin "1") (pinfunction "1_1") (pintype "passive"))
      (node (ref "U16") (pin "2") (pinfunction "PROG_2") (pintype "passive"))
    )
    (net (code "77") (name "Net-(U16-TEMP)") (class "Default")
      (node (ref "C1601") (pin "1") (pinfunction "1_1") (pintype "passive"))
      (node (ref "U16") (pin "1") (pinfunction "TEMP_1") (pintype "passive"))
    )
    (net (code "78") (name "Net-(U16-~{CHRG})") (class "Default")
      (node (ref "R1600") (pin "2") (pinfunction "2_2") (pintype "passive"))
      (node (ref "U16") (pin "7") (pinfunction "~{CHRG}_7") (pintype "passive"))
    )
    (net (code "79") (name "Net-(U16-~{STDBY})") (class "Default")
      (node (ref "R1601") (pin "2") (pinfunction "2_2") (pintype "passive"))
      (node (ref "U16") (pin "6") (pinfunction "~{STDBY}_6") (pintype "passive"))
    )
    (net (code "80") (name "POWER") (class "Default")
      (node (ref "C500") (pin "1") (pinfunction "1_1") (pintype "passive"))
      (node (ref "DC400") (pin "1") (pinfunction "1_1") (pintype "power_in"))
      (node (ref "L500") (pin "1") (pinfunction "1_1") (pintype "passive"))
      (node (ref "Q100") (pin "2") (pinfunction "D_2") (pintype "passive"))
      (node (ref "Q102") (pin "2") (pinfunction "D_2") (pintype "passive"))
      (node (ref "Q110") (pin "2") (pinfunction "D_2") (pintype "passive"))
      (node (ref "Q112") (pin "2") (pinfunction "D_2") (pintype "passive"))
      (node (ref "R160") (pin "2") (pinfunction "2_2") (pintype "passive"))
      (node (ref "R1604") (pin "2") (pinfunction "2_2") (pintype "passive"))
      (node (ref "U5") (pin "4") (pinfunction "VIN_4") (pintype "passive"))
    )
    (net (code "81") (name "SYS_VCC") (class "Default")
      (node (ref "C140") (pin "2") (pinfunction "2_2") (pintype "passive"))
      (node (ref "C141") (pin "2") (pinfunction "2_2") (pintype "passive"))
      (node (ref "C142") (pin "2") (pinfunction "2_2") (pintype "passive"))
      (node (ref "C143") (pin "2") (pinfunction "2_2") (pintype "passive"))
      (node (ref "C147") (pin "2") (pinfunction "2_2") (pintype "passive"))
      (node (ref "C301") (pin "1") (pinfunction "1_1") (pintype "passive"))
      (node (ref "L140") (pin "2") (pinfunction "2_2") (pintype "passive"))
      (node (ref "P150") (pin "1") (pinfunction "UT_1") (pintype "power_in"))
      (node (ref "R120") (pin "1") (pinfunction "1_1") (pintype "passive"))
      (node (ref "R140") (pin "1") (pinfunction "1_1") (pintype "passive"))
      (node (ref "R150") (pin "1") (pinfunction "1_1") (pintype "passive"))
      (node (ref "R151") (pin "1") (pinfunction "1_1") (pintype "passive"))
      (node (ref "R300") (pin "1") (pinfunction "1_1") (pintype "passive"))
      (node (ref "R400") (pin "1") (pinfunction "1_1") (pintype "passive"))
      (node (ref "R404") (pin "2") (pinfunction "2_2") (pintype "passive"))
      (node (ref "U1") (pin "1") (pinfunction "VBAT_1") (pintype "passive"))
      (node (ref "U1") (pin "24") (pinfunction "VDD_1_24") (pintype "passive"))
      (node (ref "U1") (pin "36") (pinfunction "VDD_2_36") (pintype "passive"))
      (node (ref "U1") (pin "48") (pinfunction "VDD_3_48") (pintype "passive"))
      (node (ref "U1") (pin "9") (pinfunction "VDDA_9") (pintype "passive"))
      (node (ref "U15") (pin "2") (pinfunction "VCC_2") (pintype "passive"))
      (node (ref "U3") (pin "2") (pinfunction "OUT_2") (pintype "passive"))
      (node (ref "U3") (pin "4") (pinfunction "OUT_4") (pintype "passive"))
      (node (ref "U4") (pin "1") (pinfunction "REST_1") (pintype "passive"))
      (node (ref "U4") (pin "8") (pinfunction "VCC_8") (pintype "passive"))
    )
    (net (code "82") (name "unconnected-(R501-Pad3)") (class "Default")
      (node (ref "R501") (pin "3") (pinfunction "3_3") (pintype "passive"))
    )
    (net (code "83") (name "unconnected-(U1-PA0-WKUP-Pad10)") (class "Default")
      (node (ref "U1") (pin "10") (pinfunction "PA0-WKUP_10") (pintype "passive"))
    )
    (net (code "84") (name "unconnected-(U1-PA4{slash}SPI1_NSS-Pad14)") (class "Default")
      (node (ref "U1") (pin "14") (pinfunction "PA4/SPI1_NSS_14") (pintype "passive"))
    )
    (net (code "85") (name "unconnected-(U1-PA8{slash}USART1_CK-Pad29)") (class "Default")
      (node (ref "U1") (pin "29") (pinfunction "PA8/USART1_CK_29") (pintype "passive"))
    )
    (net (code "86") (name "unconnected-(U1-PC13-TAMPER-RTC-Pad2)") (class "Default")
      (node (ref "U1") (pin "2") (pinfunction "PC13-TAMPER-RTC_2") (pintype "passive"))
    )
    (net (code "87") (name "unconnected-(U1-SPI2_SCK{slash}PB13-Pad26)") (class "Default")
      (node (ref "U1") (pin "26") (pinfunction "SPI2_SCK/PB13_26") (pintype "passive"))
    )
    (net (code "88") (name "unconnected-(U1-TIM2_CH2{slash}PB3-Pad39)") (class "Default")
      (node (ref "U1") (pin "39") (pinfunction "TIM2_CH2/PB3_39") (pintype "passive"))
    )
    (net (code "89") (name "unconnected-(U1-TIM3_CH1{slash}PB4-Pad40)") (class "Default")
      (node (ref "U1") (pin "40") (pinfunction "TIM3_CH1/PB4_40") (pintype "passive"))
    )
    (net (code "90") (name "unconnected-(U1-TIM3_CH2{slash}PB5-Pad41)") (class "Default")
      (node (ref "U1") (pin "41") (pinfunction "TIM3_CH2/PB5_41") (pintype "passive"))
    )
    (net (code "91") (name "unconnected-(U1-USART3_RX{slash}PB11-Pad22)") (class "Default")
      (node (ref "U1") (pin "22") (pinfunction "USART3_RX/PB11_22") (pintype "passive"))
    )
    (net (code "92") (name "unconnected-(U1-USART3_TX{slash}PB10-Pad21)") (class "Default")
      (node (ref "U1") (pin "21") (pinfunction "USART3_TX/PB10_21") (pintype "passive"))
    )
    (net (code "93") (name "unconnected-(U2-D+-Pad3)") (class "Default")
      (node (ref "U2") (pin "3") (pinfunction "D+_3") (pintype "passive"))
    )
    (net (code "94") (name "unconnected-(U2-D--Pad2)") (class "Default")
      (node (ref "U2") (pin "2") (pinfunction "D-_2") (pintype "passive"))
    )
    (net (code "95") (name "unconnected-(U2-ID-Pad4)") (class "Default")
      (node (ref "U2") (pin "4") (pinfunction "ID_4") (pintype "passive+no_connect"))
    )
    (net (code "96") (name "unconnected-(U4-ADC-Pad2)") (class "Default")
      (node (ref "U4") (pin "2") (pinfunction "ADC_2") (pintype "passive+no_connect"))
    )
    (net (code "97") (name "unconnected-(U4-CS0-Pad9)") (class "Default")
      (node (ref "U4") (pin "9") (pinfunction "CS0_9") (pintype "passive"))
    )
    (net (code "98") (name "unconnected-(U4-GPIO2-Pad17)") (class "Default")
      (node (ref "U4") (pin "17") (pinfunction "GPIO2_17") (pintype "passive"))
    )
    (net (code "99") (name "unconnected-(U4-GPIO4-Pad19)") (class "Default")
      (node (ref "U4") (pin "19") (pinfunction "GPIO4_19") (pintype "passive"))
    )
    (net (code "100") (name "unconnected-(U4-GPIO5-Pad20)") (class "Default")
      (node (ref "U4") (pin "20") (pinfunction "GPIO5_20") (pintype "passive"))
    )
    (net (code "101") (name "unconnected-(U4-GPIO9-Pad11)") (class "Default")
      (node (ref "U4") (pin "11") (pinfunction "GPIO9_11") (pintype "passive"))
    )
    (net (code "102") (name "unconnected-(U4-GPIO10-Pad12)") (class "Default")
      (node (ref "U4") (pin "12") (pinfunction "GPIO10_12") (pintype "passive"))
    )
    (net (code "103") (name "unconnected-(U4-GPIO12-Pad6)") (class "Default")
      (node (ref "U4") (pin "6") (pinfunction "GPIO12_6") (pintype "passive+no_connect"))
    )
    (net (code "104") (name "unconnected-(U4-GPIO13-Pad7)") (class "Default")
      (node (ref "U4") (pin "7") (pinfunction "GPIO13_7") (pintype "passive+no_connect"))
    )
    (net (code "105") (name "unconnected-(U4-GPIO14-Pad5)") (class "Default")
      (node (ref "U4") (pin "5") (pinfunction "GPIO14_5") (pintype "passive+no_connect"))
    )
    (net (code "106") (name "unconnected-(U4-GPIO16-Pad4)") (class "Default")
      (node (ref "U4") (pin "4") (pinfunction "GPIO16_4") (pintype "passive+no_connect"))
    )
    (net (code "107") (name "unconnected-(U4-MISO-Pad10)") (class "Default")
      (node (ref "U4") (pin "10") (pinfunction "MISO_10") (pintype "passive"))
    )
    (net (code "108") (name "unconnected-(U4-MOSI-Pad13)") (class "Default")
      (node (ref "U4") (pin "13") (pinfunction "MOSI_13") (pintype "passive"))
    )
    (net (code "109") (name "unconnected-(U4-SCLK-Pad14)") (class "Default")
      (node (ref "U4") (pin "14") (pinfunction "SCLK_14") (pintype "passive"))
    )
    (net (code "110") (name "unconnected-(U5-EN-Pad2)") (class "Default")
      (node (ref "U5") (pin "2") (pinfunction "EN_2") (pintype "passive"))
    )
  )
)
